# volume_knob.net
KiCad netlist of a schematic drawn in Altium Designer
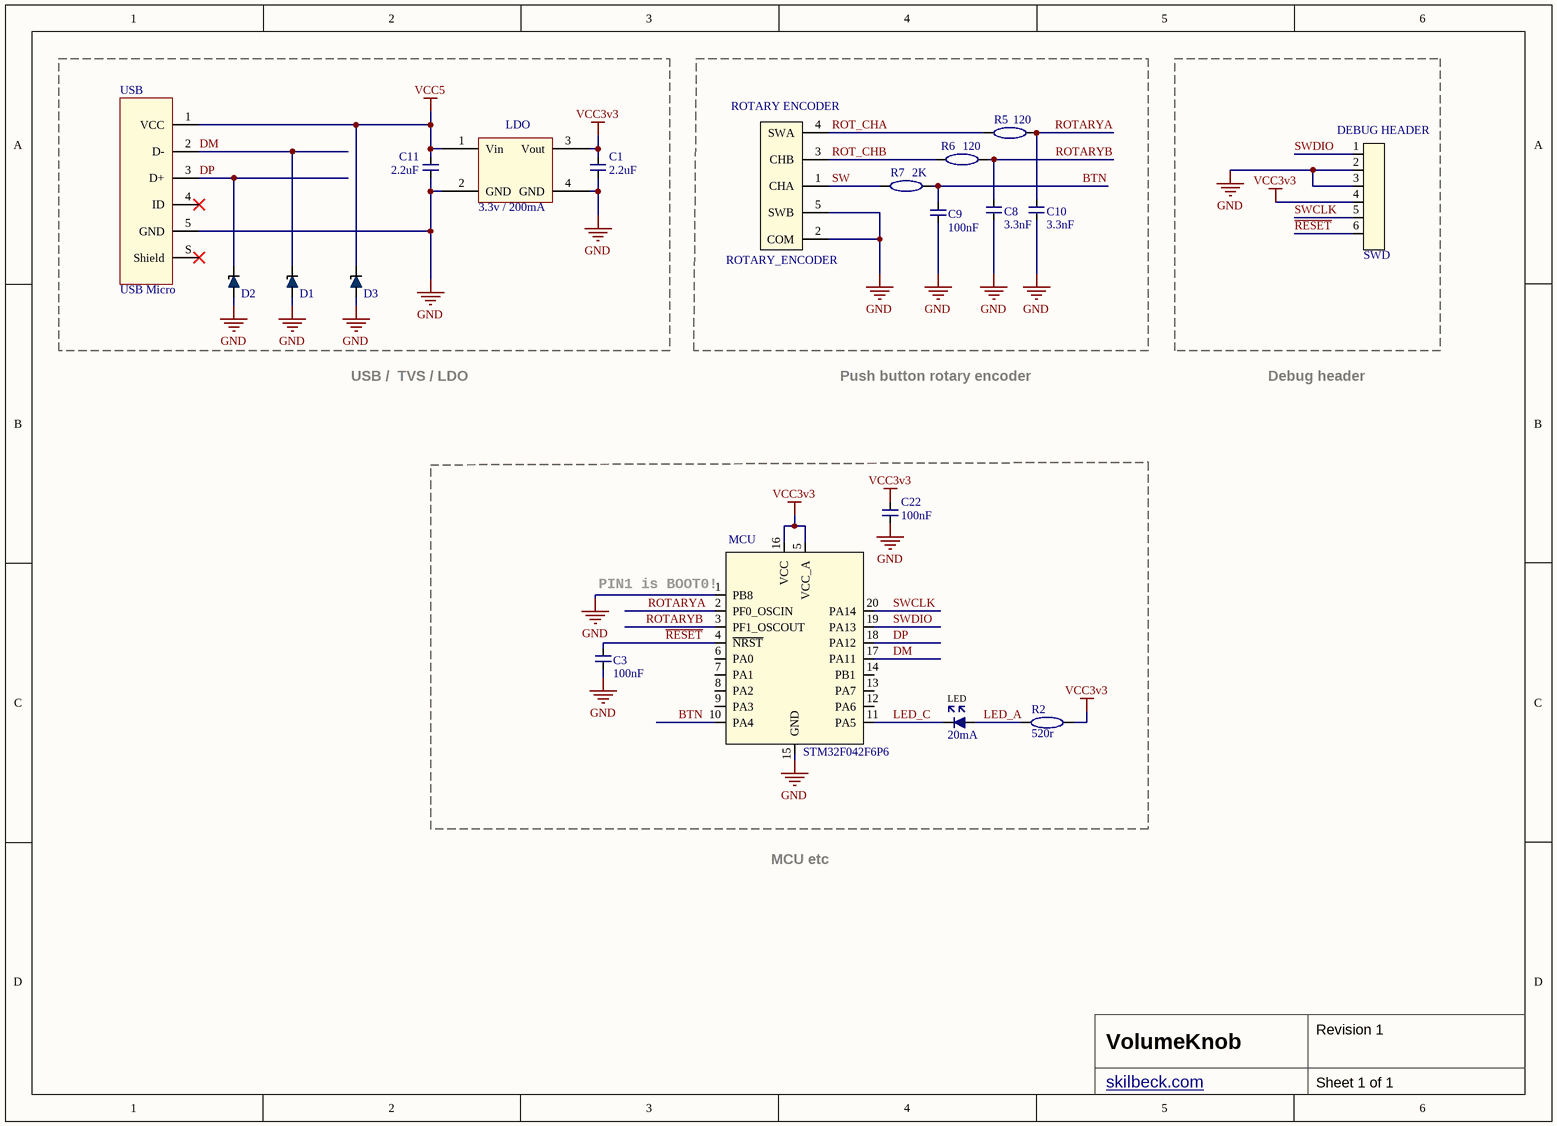
[diagram p0: volume_knob.SchDoc]

(export (version "E")
  (design (tool "Eeschema 10.0.6"))
  (components
    (comp (ref "C1")
      (value "2.2uF")
      (footprint "CAPC1608X07L")
      (description "MLCC")
      (libsource (lib "volume_knob") (part "CAP_CERAMIC"))
    )
    (comp (ref "C3")
      (value "100nF")
      (footprint "CAPC1608X07L")
      (description "Ceramic capacitor")
      (libsource (lib "volume_knob") (part "CAP_CERAMIC"))
    )
    (comp (ref "C8")
      (value "3.3nF")
      (footprint "CAPC1608X07L")
      (description "Ceramic capacitor")
      (libsource (lib "volume_knob") (part "CAP_CERAMIC"))
    )
    (comp (ref "C9")
      (value "100nF")
      (footprint "CAPC1608X07L")
      (description "Ceramic capacitor")
      (libsource (lib "volume_knob") (part "CAP_CERAMIC"))
    )
    (comp (ref "C10")
      (value "3.3nF")
      (footprint "CAPC1608X07L")
      (description "Ceramic capacitor")
      (libsource (lib "volume_knob") (part "CAP_CERAMIC"))
    )
    (comp (ref "C11")
      (value "2.2uF")
      (footprint "CAPC1608X07L")
      (description "MLCC")
      (libsource (lib "volume_knob") (part "CAP_CERAMIC"))
    )
    (comp (ref "C22")
      (value "100nF")
      (footprint "CAPC1608X07L")
      (description "MLCC")
      (libsource (lib "volume_knob") (part "CAP_CERAMIC"))
    )
    (comp (ref "D1")
      (value "TVS_DIODE")
      (footprint "SODFL98X40-2L")
      (libsource (lib "volume_knob") (part "TVS_DIODE"))
    )
    (comp (ref "D2")
      (value "TVS_DIODE")
      (footprint "SODFL98X40-2L")
      (libsource (lib "volume_knob") (part "TVS_DIODE"))
    )
    (comp (ref "D3")
      (value "TVS_DIODE")
      (footprint "SODFL98X40-2L")
      (libsource (lib "volume_knob") (part "TVS_DIODE"))
    )
    (comp (ref "DEBUG HEADER")
      (value "SWD")
      (footprint "CON5")
      (description "SWD Debug Header")
      (libsource (lib "volume_knob") (part "SWD"))
    )
    (comp (ref "LDO")
      (value "3.3v / 200mA")
      (footprint "SOT95P237X110-3L")
      (description "LDO")
      (libsource (lib "volume_knob") (part "LDO"))
    )
    (comp (ref "LED")
      (value "20mA")
      (footprint "SMT_LED_0603")
      (description "LED")
      (libsource (lib "volume_knob") (part "LED"))
    )
    (comp (ref "MCU")
      (value "STM32F042F6P6")
      (footprint "TSOP65P630X120-20L")
      (libsource (lib "volume_knob") (part "STM32F042F6P6"))
    )
    (comp (ref "R2")
      (value "520r")
      (footprint "RESC1608X05L")
      (description "Resistor 1%")
      (libsource (lib "") (part "RESISTOR_2"))
    )
    (comp (ref "R5")
      (value "120")
      (footprint "RESC1608X05L")
      (description "Resistor 1%")
      (libsource (lib "volume_knob") (part "RESISTOR"))
    )
    (comp (ref "R6")
      (value "120")
      (footprint "RESC1608X05L")
      (description "Resistor 1%")
      (libsource (lib "volume_knob") (part "RESISTOR"))
    )
    (comp (ref "R7")
      (value "2K")
      (footprint "RESC1608X05L")
      (description "Resistor 1%")
      (libsource (lib "") (part "RESISTOR_1"))
    )
    (comp (ref "ROTARY ENCODER")
      (value "ROTARY_ENCODER")
      (footprint "ENCODER")
      (description "Rotary Encoder")
      (libsource (lib "wch554e") (part "ROTARY_ENCODER"))
    )
    (comp (ref "USB")
      (value "USB Micro")
      (footprint "USB MICRO B")
      (description "USB Receptacle")
      (libsource (lib "wch554e") (part "USB_SOCKET"))
    )
  )
  (nets
    (net (code "1") (name "/BTN") (class "Default")
      (node (ref "C9") (pin "2") (pinfunction "B_2") (pintype "passive"))
      (node (ref "MCU") (pin "10") (pinfunction "PA4_10") (pintype "power_in"))
      (node (ref "R7") (pin "1") (pinfunction "A_1") (pintype "passive"))
    )
    (net (code "2") (name "/DM") (class "Default")
      (node (ref "D1") (pin "1") (pinfunction "K_1") (pintype "passive"))
      (node (ref "MCU") (pin "17") (pinfunction "PA11_17") (pintype "power_in"))
      (node (ref "USB") (pin "2") (pinfunction "D-_2") (pintype "passive"))
    )
    (net (code "3") (name "/DP") (class "Default")
      (node (ref "D2") (pin "1") (pinfunction "K_1") (pintype "passive"))
      (node (ref "MCU") (pin "18") (pinfunction "PA12_18") (pintype "power_in"))
      (node (ref "USB") (pin "3") (pinfunction "D+_3") (pintype "passive"))
    )
    (net (code "4") (name "/LED_A") (class "Default")
      (node (ref "LED") (pin "1") (pinfunction "CATHODE_1") (pintype "passive"))
      (node (ref "R2") (pin "1") (pinfunction "A_1") (pintype "passive"))
    )
    (net (code "5") (name "/LED_C") (class "Default")
      (node (ref "LED") (pin "2") (pinfunction "ANODE_2") (pintype "passive"))
      (node (ref "MCU") (pin "11") (pinfunction "PA5_11") (pintype "power_in"))
    )
    (net (code "6") (name "/RESET") (class "Default")
      (node (ref "C3") (pin "2") (pinfunction "B_2") (pintype "passive"))
      (node (ref "DEBUG HEADER") (pin "6") (pintype "power_in"))
      (node (ref "MCU") (pin "4") (pinfunction "NRST_4") (pintype "power_in"))
    )
    (net (code "7") (name "/ROTARYA") (class "Default")
      (node (ref "C10") (pin "1") (pinfunction "A_1") (pintype "passive"))
      (node (ref "MCU") (pin "2") (pinfunction "PF0_OSCIN_2") (pintype "power_in"))
      (node (ref "R5") (pin "2") (pinfunction "B_2") (pintype "passive"))
    )
    (net (code "8") (name "/ROTARYB") (class "Default")
      (node (ref "C8") (pin "2") (pinfunction "B_2") (pintype "passive"))
      (node (ref "MCU") (pin "3") (pinfunction "PF1_OSCOUT_3") (pintype "power_in"))
      (node (ref "R6") (pin "2") (pinfunction "B_2") (pintype "passive"))
    )
    (net (code "9") (name "/ROT_CHA") (class "Default")
      (node (ref "R5") (pin "1") (pinfunction "A_1") (pintype "passive"))
      (node (ref "ROTARY ENCODER") (pin "4") (pinfunction "SWA_4") (pintype "passive"))
    )
    (net (code "10") (name "/ROT_CHB") (class "Default")
      (node (ref "R6") (pin "1") (pinfunction "A_1") (pintype "passive"))
      (node (ref "ROTARY ENCODER") (pin "3") (pinfunction "CHB_3") (pintype "passive"))
    )
    (net (code "11") (name "/SW") (class "Default")
      (node (ref "R7") (pin "2") (pinfunction "B_2") (pintype "passive"))
      (node (ref "ROTARY ENCODER") (pin "1") (pinfunction "CHA_1") (pintype "passive"))
    )
    (net (code "12") (name "/SWCLK") (class "Default")
      (node (ref "DEBUG HEADER") (pin "5") (pintype "power_in"))
      (node (ref "MCU") (pin "20") (pinfunction "PA14_20") (pintype "power_in"))
    )
    (net (code "13") (name "/SWDIO") (class "Default")
      (node (ref "DEBUG HEADER") (pin "1") (pintype "passive"))
      (node (ref "MCU") (pin "19") (pinfunction "PA13_19") (pintype "power_in"))
    )
    (net (code "14") (name "GND") (class "Default")
      (node (ref "C1") (pin "1") (pinfunction "A_1") (pintype "passive"))
      (node (ref "C10") (pin "2") (pinfunction "B_2") (pintype "passive"))
      (node (ref "C11") (pin "1") (pinfunction "A_1") (pintype "passive"))
      (node (ref "C22") (pin "1") (pinfunction "A_1") (pintype "passive"))
      (node (ref "C3") (pin "1") (pinfunction "A_1") (pintype "passive"))
      (node (ref "C8") (pin "1") (pinfunction "A_1") (pintype "passive"))
      (node (ref "C9") (pin "1") (pinfunction "A_1") (pintype "passive"))
      (node (ref "D1") (pin "2") (pinfunction "A_2") (pintype "passive"))
      (node (ref "D2") (pin "2") (pinfunction "A_2") (pintype "passive"))
      (node (ref "D3") (pin "2") (pinfunction "A_2") (pintype "passive"))
      (node (ref "DEBUG HEADER") (pin "2") (pintype "passive"))
      (node (ref "DEBUG HEADER") (pin "3") (pintype "passive"))
      (node (ref "LDO") (pin "2") (pinfunction "GND_2") (pintype "passive"))
      (node (ref "LDO") (pin "4") (pinfunction "GND_4") (pintype "passive"))
      (node (ref "MCU") (pin "1") (pinfunction "PB8_1") (pintype "power_in"))
      (node (ref "MCU") (pin "15") (pinfunction "GND_15") (pintype "power_in"))
      (node (ref "ROTARY ENCODER") (pin "2") (pinfunction "COM_2") (pintype "passive"))
      (node (ref "ROTARY ENCODER") (pin "5") (pinfunction "SWB_5") (pintype "passive"))
      (node (ref "USB") (pin "5") (pinfunction "GND_5") (pintype "passive"))
    )
    (net (code "15") (name "VCC3v3") (class "Default")
      (node (ref "C1") (pin "2") (pinfunction "B_2") (pintype "passive"))
      (node (ref "C22") (pin "2") (pinfunction "B_2") (pintype "passive"))
      (node (ref "DEBUG HEADER") (pin "4") (pintype "passive"))
      (node (ref "LDO") (pin "3") (pinfunction "Vout_3") (pintype "passive"))
      (node (ref "MCU") (pin "16") (pinfunction "VCC_16") (pintype "power_in"))
      (node (ref "MCU") (pin "5") (pinfunction "VCC_A_5") (pintype "power_in"))
      (node (ref "R2") (pin "2") (pinfunction "B_2") (pintype "passive"))
    )
    (net (code "16") (name "VCC5") (class "Default")
      (node (ref "C11") (pin "2") (pinfunction "B_2") (pintype "passive"))
      (node (ref "D3") (pin "1") (pinfunction "K_1") (pintype "passive"))
      (node (ref "LDO") (pin "1") (pinfunction "Vin_1") (pintype "passive"))
      (node (ref "USB") (pin "1") (pinfunction "VCC_1") (pintype "passive"))
    )
    (net (code "17") (name "unconnected-(MCU-PA0-Pad6)") (class "Default")
      (node (ref "MCU") (pin "6") (pinfunction "PA0_6") (pintype "power_in"))
    )
    (net (code "18") (name "unconnected-(MCU-PA1-Pad7)") (class "Default")
      (node (ref "MCU") (pin "7") (pinfunction "PA1_7") (pintype "power_in"))
    )
    (net (code "19") (name "unconnected-(MCU-PA2-Pad8)") (class "Default")
      (node (ref "MCU") (pin "8") (pinfunction "PA2_8") (pintype "power_in"))
    )
    (net (code "20") (name "unconnected-(MCU-PA3-Pad9)") (class "Default")
      (node (ref "MCU") (pin "9") (pinfunction "PA3_9") (pintype "power_in"))
    )
    (net (code "21") (name "unconnected-(MCU-PA6-Pad12)") (class "Default")
      (node (ref "MCU") (pin "12") (pinfunction "PA6_12") (pintype "power_in"))
    )
    (net (code "22") (name "unconnected-(MCU-PA7-Pad13)") (class "Default")
      (node (ref "MCU") (pin "13") (pinfunction "PA7_13") (pintype "power_in"))
    )
    (net (code "23") (name "unconnected-(MCU-PB1-Pad14)") (class "Default")
      (node (ref "MCU") (pin "14") (pinfunction "PB1_14") (pintype "power_in"))
    )
    (net (code "24") (name "unconnected-(USB-ID-Pad4)") (class "Default")
      (node (ref "USB") (pin "4") (pinfunction "ID_4") (pintype "passive+no_connect"))
    )
    (net (code "25") (name "unconnected-(USB-Shield-PadS)") (class "Default")
      (node (ref "USB") (pin "S") (pinfunction "Shield_S") (pintype "passive+no_connect"))
    )
  )
)
